# MovimientoALIM.net
KiCad netlist of a schematic drawn in EAGLE
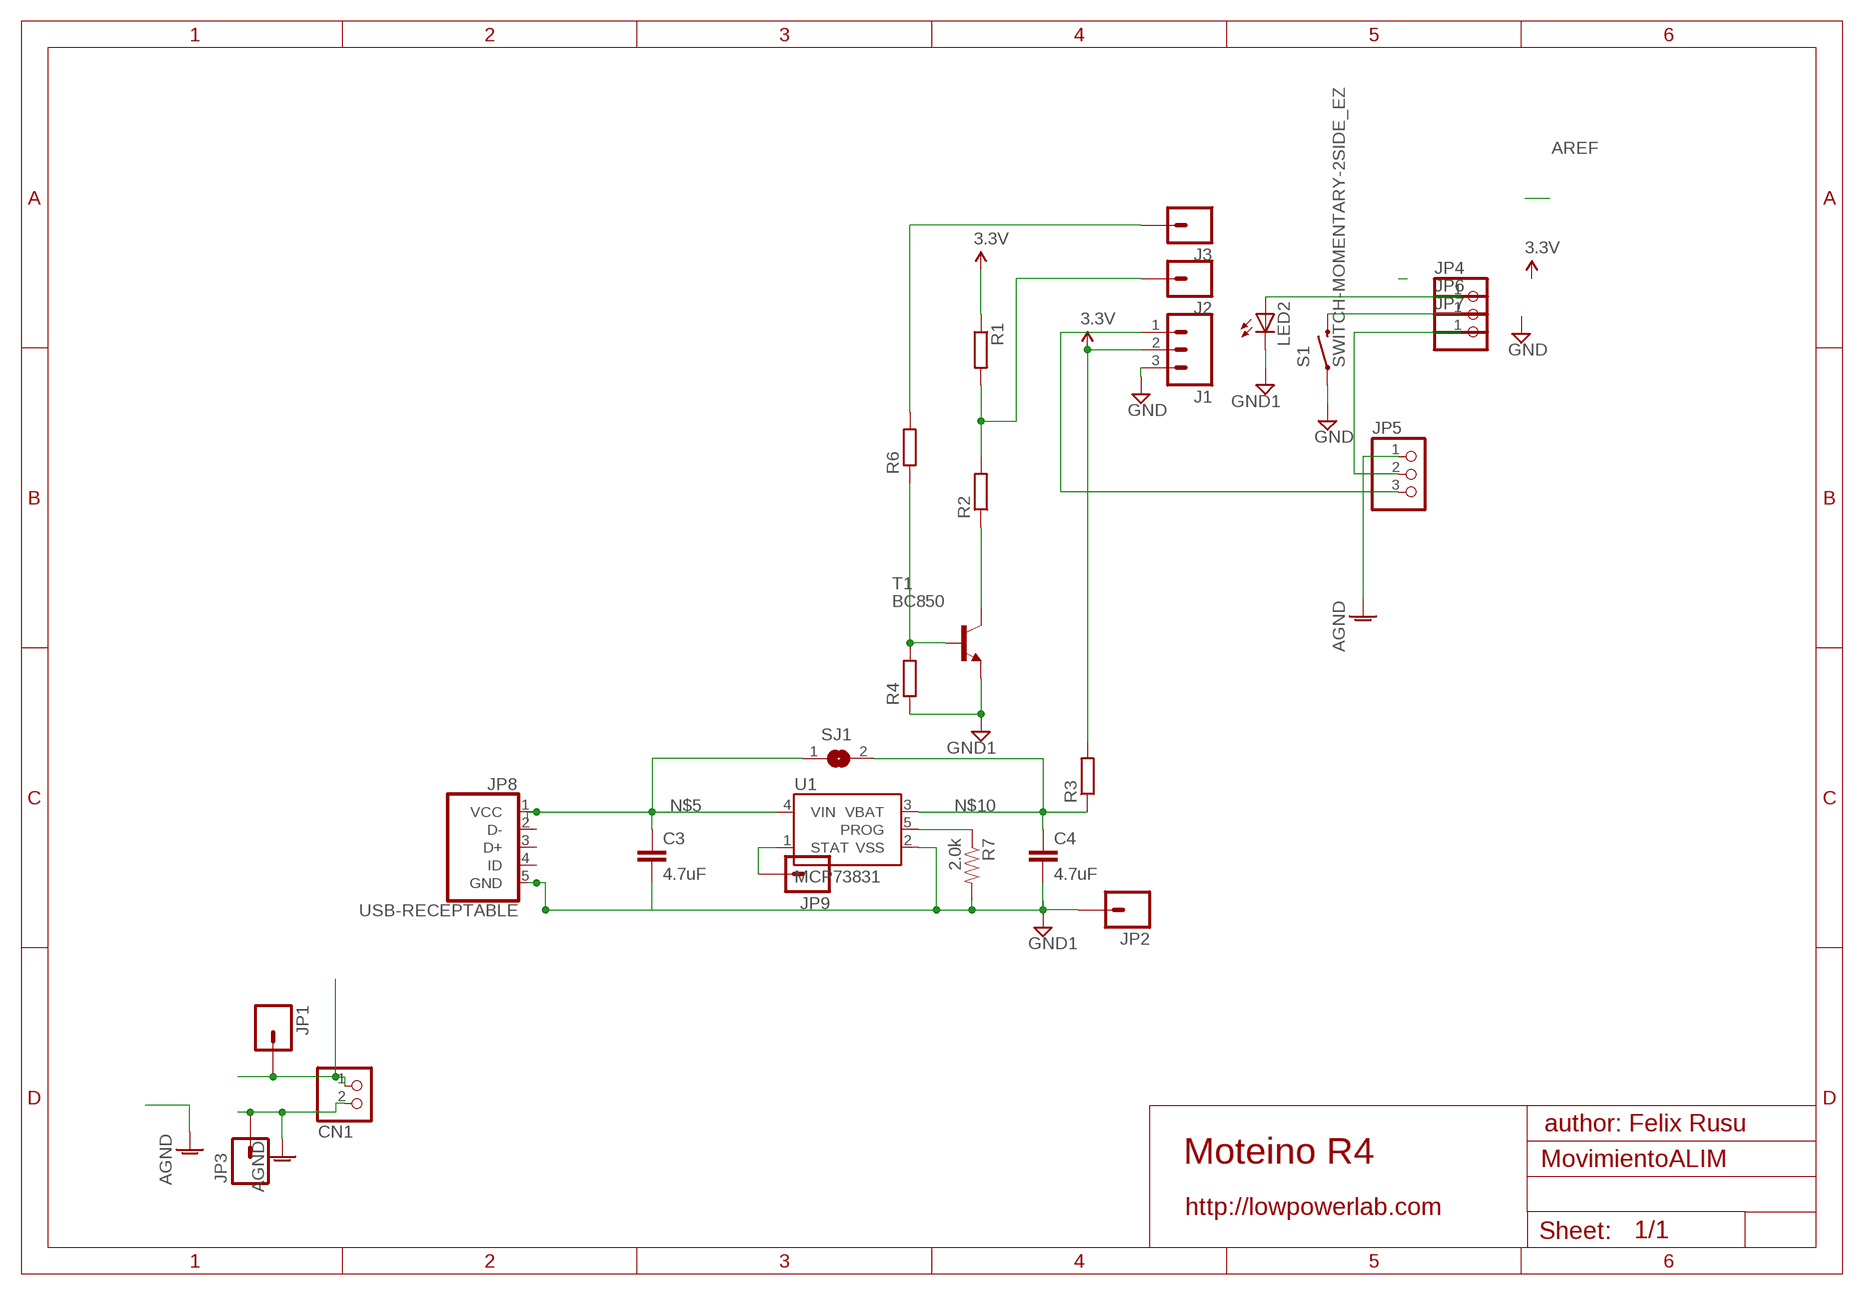
[diagram p0: schematic, sheet 1]

(export (version "E")
  (design (tool "Eeschema 10.0.6"))
  (components
    (comp (ref "C3")
      (value "4.7uF")
      (footprint "eagle-import:0603-CAP")
      (libsource (lib "eagle-import") (part "4.7UF-6.3V-10%(0603)0603"))
    )
    (comp (ref "C4")
      (value "4.7uF")
      (footprint "eagle-import:0603-CAP")
      (libsource (lib "eagle-import") (part "4.7UF-6.3V-10%(0603)0603"))
    )
    (comp (ref "CN1")
      (value "JST_2PIN-SMT")
      (footprint "eagle-import:JST-PH-2-SMT")
      (libsource (lib "eagle-import") (part "JST_2PIN-SMT"))
    )
    (comp (ref "J1")
      (value "M03PTH")
      (footprint "eagle-import:1X03")
      (libsource (lib "eagle-import") (part "M03PTH"))
    )
    (comp (ref "J2")
      (value "M01PTH")
      (footprint "eagle-import:1X01")
      (libsource (lib "eagle-import") (part "M01PTH"))
    )
    (comp (ref "J3")
      (value "M01PTH")
      (footprint "eagle-import:1X01")
      (libsource (lib "eagle-import") (part "M01PTH"))
    )
    (comp (ref "JP1")
      (value "M01PTH")
      (footprint "eagle-import:1X01")
      (libsource (lib "eagle-import") (part "M01PTH"))
    )
    (comp (ref "JP2")
      (value "M01PTH")
      (footprint "eagle-import:1X01")
      (libsource (lib "eagle-import") (part "M01PTH"))
    )
    (comp (ref "JP3")
      (value "M01PTH")
      (footprint "eagle-import:1X01")
      (libsource (lib "eagle-import") (part "M01PTH"))
    )
    (comp (ref "JP4")
      (value "PINHD-1X1")
      (footprint "eagle-import:1X01")
      (libsource (lib "eagle-import") (part "PINHD-1X1"))
    )
    (comp (ref "JP5")
      (value "PINHD-1X3")
      (footprint "eagle-import:1X03")
      (libsource (lib "eagle-import") (part "PINHD-1X3"))
    )
    (comp (ref "JP6")
      (value "PINHD-1X1")
      (footprint "eagle-import:1X01")
      (libsource (lib "eagle-import") (part "PINHD-1X1"))
    )
    (comp (ref "JP7")
      (value "PINHD-1X1")
      (footprint "eagle-import:1X01")
      (libsource (lib "eagle-import") (part "PINHD-1X1"))
    )
    (comp (ref "JP8")
      (value "USB-RECEPTABLE")
      (footprint "eagle-import:FCI-10103594-0001LF")
      (libsource (lib "eagle-import") (part "USB-RECEPTABLE"))
    )
    (comp (ref "JP9")
      (value "M01PTH")
      (footprint "eagle-import:1X01")
      (libsource (lib "eagle-import") (part "M01PTH"))
    )
    (comp (ref "LED2")
      (value "LED3MM")
      (footprint "eagle-import:LED3MM")
      (libsource (lib "eagle-import") (part "LED3MM"))
    )
    (comp (ref "R1")
      (value "R-EU_0204/7")
      (footprint "eagle-import:0204_7")
      (libsource (lib "eagle-import") (part "R-EU_0204/7"))
    )
    (comp (ref "R2")
      (value "R-EU_0204/7")
      (footprint "eagle-import:0204_7")
      (libsource (lib "eagle-import") (part "R-EU_0204/7"))
    )
    (comp (ref "R3")
      (value "R-EU_M1206")
      (footprint "eagle-import:M1206")
      (libsource (lib "eagle-import") (part "R-EU_M1206"))
    )
    (comp (ref "R4")
      (value "R-EU_M1206")
      (footprint "eagle-import:M1206")
      (libsource (lib "eagle-import") (part "R-EU_M1206"))
    )
    (comp (ref "R6")
      (value "R-EU_M1206")
      (footprint "eagle-import:M1206")
      (libsource (lib "eagle-import") (part "R-EU_M1206"))
    )
    (comp (ref "R7")
      (value "2.0k")
      (footprint "eagle-import:0603-RES")
      (libsource (lib "eagle-import") (part "2.0KOHM1/10W5%(0603)"))
    )
    (comp (ref "S1")
      (value "SWITCH-MOMENTARY-2SIDE_EZ")
      (footprint "eagle-import:TACTILE-PTH-SIDEEZ")
      (libsource (lib "eagle-import") (part "SWITCH-MOMENTARY-2SIDE_EZ"))
    )
    (comp (ref "SJ1") (value "SJ") (footprint "eagle-import:SJ") (libsource (lib "eagle-import") (part "SJ")))
    (comp (ref "T1")
      (value "BC850")
      (footprint "eagle-import:SOT23")
      (libsource (lib "eagle-import") (part "BC850"))
    )
    (comp (ref "U1")
      (value "MCP73831")
      (footprint "eagle-import:SOT23-5")
      (libsource (lib "eagle-import") (part "MCP73831"))
    )
  )
  (nets
    (net (code "2") (name "/N$5") (class "Default")
      (node (ref "C3") (pin "1") (pinfunction "1_1") (pintype "passive"))
      (node (ref "JP8") (pin "1") (pinfunction "VCC_1") (pintype "bidirectional"))
      (node (ref "SJ1") (pin "1") (pinfunction "1_1") (pintype "passive"))
      (node (ref "U1") (pin "4") (pinfunction "VIN_4") (pintype "power_in"))
    )
    (net (code "3") (name "/N$10") (class "Default")
      (node (ref "C4") (pin "1") (pinfunction "1_1") (pintype "passive"))
      (node (ref "R3") (pin "1") (pinfunction "1_1") (pintype "passive"))
      (node (ref "SJ1") (pin "2") (pinfunction "2_2") (pintype "passive"))
      (node (ref "U1") (pin "3") (pinfunction "VBAT_3") (pintype "power_in"))
    )
    (net (code "4") (name "3.3V") (class "Default")
      (node (ref "J1") (pin "2") (pinfunction "2_2") (pintype "passive"))
      (node (ref "R1") (pin "1") (pinfunction "1_1") (pintype "passive"))
      (node (ref "R3") (pin "2") (pinfunction "2_2") (pintype "passive"))
    )
    (net (code "5") (name "AGND") (class "Default")
      (node (ref "CN1") (pin "2") (pinfunction "1_2") (pintype "passive"))
      (node (ref "JP3") (pin "1") (pinfunction "1_1") (pintype "passive"))
      (node (ref "JP5") (pin "1") (pinfunction "1_1") (pintype "passive"))
    )
    (net (code "6") (name "GND") (class "Default")
      (node (ref "J1") (pin "3") (pinfunction "3_3") (pintype "passive"))
      (node (ref "S1") (pin "1") (pinfunction "1_1") (pintype "passive"))
    )
    (net (code "7") (name "GND1") (class "Default")
      (node (ref "C3") (pin "2") (pinfunction "2_2") (pintype "passive"))
      (node (ref "C4") (pin "2") (pinfunction "2_2") (pintype "passive"))
      (node (ref "JP2") (pin "1") (pinfunction "1_1") (pintype "passive"))
      (node (ref "JP8") (pin "5") (pinfunction "GND_5") (pintype "bidirectional"))
      (node (ref "LED2") (pin "K") (pinfunction "C_K") (pintype "passive"))
      (node (ref "R4") (pin "1") (pinfunction "1_1") (pintype "passive"))
      (node (ref "R7") (pin "2") (pinfunction "2_2") (pintype "passive"))
      (node (ref "T1") (pin "2") (pinfunction "E_2") (pintype "passive"))
      (node (ref "U1") (pin "2") (pinfunction "VSS_2") (pintype "power_in"))
    )
    (net (code "8") (name "Net-(CN1-2)") (class "Default")
      (node (ref "CN1") (pin "1") (pinfunction "2_1") (pintype "passive"))
      (node (ref "JP1") (pin "1") (pinfunction "1_1") (pintype "passive"))
    )
    (net (code "9") (name "Net-(J1-Pad1)") (class "Default")
      (node (ref "J1") (pin "1") (pinfunction "1_1") (pintype "passive"))
      (node (ref "JP5") (pin "3") (pinfunction "3_3") (pintype "passive"))
    )
    (net (code "10") (name "Net-(J2-Pad1)") (class "Default")
      (node (ref "J2") (pin "1") (pinfunction "1_1") (pintype "passive"))
      (node (ref "R1") (pin "2") (pinfunction "2_2") (pintype "passive"))
      (node (ref "R2") (pin "2") (pinfunction "2_2") (pintype "passive"))
    )
    (net (code "11") (name "Net-(J3-Pad1)") (class "Default")
      (node (ref "J3") (pin "1") (pinfunction "1_1") (pintype "passive"))
      (node (ref "R6") (pin "2") (pinfunction "2_2") (pintype "passive"))
    )
    (net (code "12") (name "Net-(JP4-Pad1)") (class "Default")
      (node (ref "JP4") (pin "1") (pinfunction "1_1") (pintype "passive"))
      (node (ref "LED2") (pin "A") (pinfunction "A_A") (pintype "passive"))
    )
    (net (code "13") (name "Net-(JP5-Pad2)") (class "Default")
      (node (ref "JP5") (pin "2") (pinfunction "2_2") (pintype "passive"))
      (node (ref "JP7") (pin "1") (pinfunction "1_1") (pintype "passive"))
    )
    (net (code "14") (name "Net-(JP6-Pad1)") (class "Default")
      (node (ref "JP6") (pin "1") (pinfunction "1_1") (pintype "passive"))
      (node (ref "S1") (pin "2") (pinfunction "2_2") (pintype "passive"))
    )
    (net (code "15") (name "Net-(T1-B)") (class "Default")
      (node (ref "R4") (pin "2") (pinfunction "2_2") (pintype "passive"))
      (node (ref "R6") (pin "1") (pinfunction "1_1") (pintype "passive"))
      (node (ref "T1") (pin "1") (pinfunction "B_1") (pintype "passive"))
    )
    (net (code "16") (name "Net-(T1-C)") (class "Default")
      (node (ref "R2") (pin "1") (pinfunction "1_1") (pintype "passive"))
      (node (ref "T1") (pin "3") (pinfunction "C_3") (pintype "passive"))
    )
    (net (code "17") (name "Net-(U1-PROG)") (class "Default")
      (node (ref "R7") (pin "1") (pinfunction "1_1") (pintype "passive"))
      (node (ref "U1") (pin "5") (pinfunction "PROG_5") (pintype "input"))
    )
    (net (code "18") (name "Net-(U1-STAT)") (class "Default")
      (node (ref "JP9") (pin "1") (pinfunction "1_1") (pintype "passive"))
      (node (ref "U1") (pin "1") (pinfunction "STAT_1") (pintype "output"))
    )
    (net (code "19") (name "unconnected-(JP8-D+-Pad3)") (class "Default")
      (node (ref "JP8") (pin "3") (pinfunction "D+_3") (pintype "bidirectional"))
    )
    (net (code "20") (name "unconnected-(JP8-D--Pad2)") (class "Default")
      (node (ref "JP8") (pin "2") (pinfunction "D-_2") (pintype "bidirectional"))
    )
    (net (code "21") (name "unconnected-(JP8-ID-Pad4)") (class "Default")
      (node (ref "JP8") (pin "4") (pinfunction "ID_4") (pintype "bidirectional"))
    )
  )
)
